# 1_zasilanie_ascii.net
KiCad netlist of a schematic drawn in Altium Designer
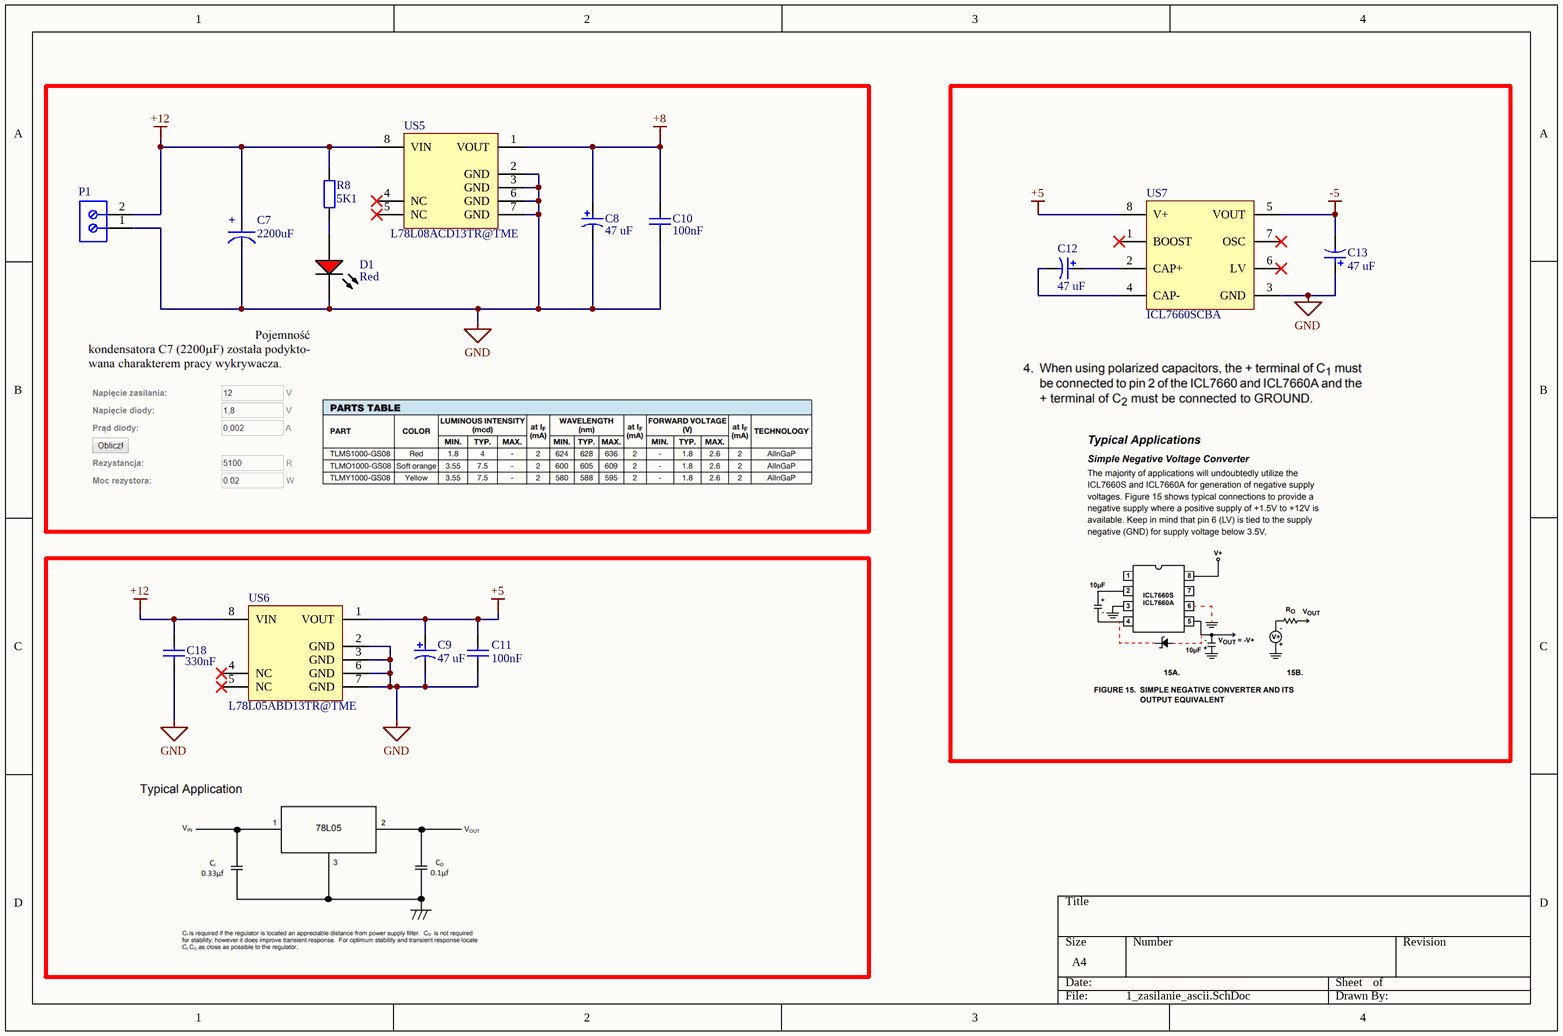
[diagram p0: 1_zasilanie_ascii.SchDoc]

(export (version "E")
  (design (tool "Eeschema 10.0.6"))
  (components
    (comp (ref "C7")
      (value "Cap Electrolytic")
      (footprint "Capacitors_MT_Library:18 X 25mm Radial 7.5mm")
      (description "CAPACITOR ALUM 2200UF 20% 35V RADIAL")
      (fields (field (name "CAPACITANCE") "2200uF"))
      (libsource (lib "MT_Library") (part "Cap Electrolytic"))
    )
    (comp (ref "C8")
      (value "UUD1E470MCL1GS")
      (footprint "NIC-CAPA2-6.3X5.8_V")
      (fields (field (name "MANUFACTURER") "Nichicon") (field (name "RATED CAPACITANCE") "47 uF"))
      (libsource (lib "Altium Content Vault") (part "NIC-CAP-P-2"))
    )
    (comp (ref "C9")
      (value "UUD1E470MCL1GS")
      (footprint "NIC-CAPA2-6.3X5.8_V")
      (fields (field (name "MANUFACTURER") "Nichicon") (field (name "RATED CAPACITANCE") "47 uF"))
      (libsource (lib "Altium Content Vault") (part "NIC-CAP-P-2"))
    )
    (comp (ref "C10")
      (value "CL10B104KA8NNNC@TME")
      (footprint "0603")
      (description "Capacitor")
      (fields (field (name "CAPACITANCE") "100nF"))
      (libsource (lib "MT_Library") (part "Cap"))
    )
    (comp (ref "C11")
      (value "CL10B104KA8NNNC@TME")
      (footprint "0603")
      (description "Capacitor")
      (fields (field (name "CAPACITANCE") "100nF"))
      (libsource (lib "MT_Library") (part "Cap"))
    )
    (comp (ref "C12")
      (value "UUD1E470MCL1GS")
      (footprint "NIC-CAPA2-6.3X5.8_V")
      (fields (field (name "MANUFACTURER") "Nichicon") (field (name "RATED CAPACITANCE") "47 uF"))
      (libsource (lib "Altium Content Vault") (part "NIC-CAP-P-2"))
    )
    (comp (ref "C13")
      (value "UUD1E470MCL1GS")
      (footprint "NIC-CAPA2-6.3X5.8_V")
      (fields (field (name "MANUFACTURER") "Nichicon") (field (name "RATED CAPACITANCE") "47 uF"))
      (libsource (lib "Altium Content Vault") (part "NIC-CAP-P-2"))
    )
    (comp (ref "C18")
      (value "330nF")
      (footprint "CAPC1608X90X35ML15T15")
      (fields
        (field (name "PART NUMBER") "0603YD334KAT2A")
        (field (name "MANUFACTURER") "AVX Interconnect / Elco")
      )
      (libsource (lib "Altium Content Vault") (part "CAP"))
    )
    (comp (ref "D1")
      (value "TLMS1000-GS08")
      (footprint "VISH-TLMS1000_V")
      (description "Low Current LED, 40 mW, 1.8 V, -40 to 100 degC, 2-Pin SMD (0603), RoHS, Tape and Reel")
      (fields (field (name "LED COLOUR") "Red") (field (name "MANUFACTURER") "Vishay"))
      (libsource (lib "Altium Content Vault") (part "LED-RED-AK-2"))
    )
    (comp (ref "P1")
      (value "282836-2@TME")
      (footprint "TECO-282836-2_V")
      (description "Female Header, Pitch 5 mm, 1 x 2 Position, Height 10 mm, Tail Length 3.5 mm, Rohs, Bulk")
      (fields (field (name "VOLTAGE") "300V") (field (name "MANUFACTURER") "TE Connectivity"))
      (libsource (lib "Altium Content Vault") (part "CN-1P-F-TB2"))
    )
    (comp (ref "R8")
      (value "5K1")
      (footprint "R1206")
      (description "Resistor")
      (fields (field (name "Comment") "1206S4J0102T5E@TME"))
      (libsource (lib "MT_Library") (part "Res"))
    )
    (comp (ref "US5")
      (value "L78L08ACD13TR@TME")
      (footprint "SO8_M")
      (description "Positive Voltage Regulator, 8V, 8-Pin SO, Tape and Reel")
      (libsource (lib "Altium Content Vault") (part "PM-REG-7805-IL8"))
    )
    (comp (ref "US6")
      (value "L78L05ABD13TR@TME")
      (footprint "SO8_N")
      (description "Positive Voltage Regulator, 5V, 8-Pin SO, Tape and Reel")
      (libsource (lib "Altium Content Vault") (part "PM-REG-7805-IL8"))
    )
    (comp (ref "US7")
      (value "ICL7660SCBA")
      (footprint "INTS-SOIC-8_V")
      (fields (field (name "MANUFACTURER") "Intersil"))
      (libsource (lib "Altium Content Vault") (part "INTS-ICL7660S-8"))
    )
  )
  (nets
    (net (code "1") (name "+5") (class "Default")
      (node (ref "C11") (pin "1") (pinfunction "1_1") (pintype "passive"))
      (node (ref "C9") (pin "1") (pinfunction "1_1") (pintype "passive"))
      (node (ref "US6") (pin "1") (pinfunction "VOUT_1") (pintype "power_in"))
      (node (ref "US7") (pin "8") (pinfunction "V+_8") (pintype "power_in"))
    )
    (net (code "2") (name "+8") (class "Default")
      (node (ref "C10") (pin "1") (pinfunction "1_1") (pintype "passive"))
      (node (ref "C8") (pin "1") (pinfunction "1_1") (pintype "passive"))
      (node (ref "US5") (pin "1") (pinfunction "VOUT_1") (pintype "power_in"))
    )
    (net (code "3") (name "+12") (class "Default")
      (node (ref "C18") (pin "1") (pinfunction "1_1") (pintype "passive"))
      (node (ref "C7") (pin "2") (pinfunction "+_2") (pintype "passive"))
      (node (ref "P1") (pin "2") (pinfunction "-_2") (pintype "power_in"))
      (node (ref "R8") (pin "2") (pinfunction "2_2") (pintype "passive"))
      (node (ref "US5") (pin "8") (pinfunction "VIN_8") (pintype "power_in"))
      (node (ref "US6") (pin "8") (pinfunction "VIN_8") (pintype "power_in"))
    )
    (net (code "4") (name "-5") (class "Default")
      (node (ref "C13") (pin "2") (pinfunction "2_2") (pintype "passive"))
      (node (ref "US7") (pin "5") (pinfunction "VOUT_5") (pintype "power_in"))
    )
    (net (code "5") (name "GND") (class "Default")
      (node (ref "C10") (pin "2") (pinfunction "2_2") (pintype "passive"))
      (node (ref "C11") (pin "2") (pinfunction "2_2") (pintype "passive"))
      (node (ref "C13") (pin "1") (pinfunction "1_1") (pintype "passive"))
      (node (ref "C18") (pin "2") (pinfunction "2_2") (pintype "passive"))
      (node (ref "C7") (pin "1") (pinfunction "-_1") (pintype "passive"))
      (node (ref "C8") (pin "2") (pinfunction "2_2") (pintype "passive"))
      (node (ref "C9") (pin "2") (pinfunction "2_2") (pintype "passive"))
      (node (ref "D1") (pin "2") (pinfunction "K_2") (pintype "passive"))
      (node (ref "P1") (pin "1") (pinfunction "+_1") (pintype "power_in"))
      (node (ref "US5") (pin "2") (pinfunction "GND_2") (pintype "power_in"))
      (node (ref "US5") (pin "3") (pinfunction "GND_3") (pintype "power_in"))
      (node (ref "US5") (pin "6") (pinfunction "GND_6") (pintype "power_in"))
      (node (ref "US5") (pin "7") (pinfunction "GND_7") (pintype "power_in"))
      (node (ref "US6") (pin "2") (pinfunction "GND_2") (pintype "power_in"))
      (node (ref "US6") (pin "3") (pinfunction "GND_3") (pintype "power_in"))
      (node (ref "US6") (pin "6") (pinfunction "GND_6") (pintype "power_in"))
      (node (ref "US6") (pin "7") (pinfunction "GND_7") (pintype "power_in"))
      (node (ref "US7") (pin "3") (pinfunction "GND_3") (pintype "power_in"))
    )
    (net (code "6") (name "Net-(D1-A)") (class "Default")
      (node (ref "D1") (pin "1") (pinfunction "A_1") (pintype "passive"))
      (node (ref "R8") (pin "1") (pinfunction "1_1") (pintype "passive"))
    )
    (net (code "7") (name "Net-(US7-CAP+)") (class "Default")
      (node (ref "C12") (pin "1") (pinfunction "1_1") (pintype "passive"))
      (node (ref "US7") (pin "2") (pinfunction "CAP+_2") (pintype "passive"))
    )
    (net (code "8") (name "Net-(US7-CAP-)") (class "Default")
      (node (ref "C12") (pin "2") (pinfunction "2_2") (pintype "passive"))
      (node (ref "US7") (pin "4") (pinfunction "CAP-_4") (pintype "passive"))
    )
    (net (code "9") (name "unconnected-(US5-NC-Pad4)") (class "Default")
      (node (ref "US5") (pin "4") (pinfunction "NC_4") (pintype "passive+no_connect"))
    )
    (net (code "10") (name "unconnected-(US5-NC-Pad5)") (class "Default")
      (node (ref "US5") (pin "5") (pinfunction "NC_5") (pintype "passive+no_connect"))
    )
    (net (code "11") (name "unconnected-(US6-NC-Pad4)") (class "Default")
      (node (ref "US6") (pin "4") (pinfunction "NC_4") (pintype "passive+no_connect"))
    )
    (net (code "12") (name "unconnected-(US6-NC-Pad5)") (class "Default")
      (node (ref "US6") (pin "5") (pinfunction "NC_5") (pintype "passive+no_connect"))
    )
    (net (code "13") (name "unconnected-(US7-BOOST-Pad1)") (class "Default")
      (node (ref "US7") (pin "1") (pinfunction "BOOST_1") (pintype "passive+no_connect"))
    )
    (net (code "14") (name "unconnected-(US7-LV-Pad6)") (class "Default")
      (node (ref "US7") (pin "6") (pinfunction "LV_6") (pintype "power_in+no_connect"))
    )
    (net (code "15") (name "unconnected-(US7-OSC-Pad7)") (class "Default")
      (node (ref "US7") (pin "7") (pinfunction "OSC_7") (pintype "passive+no_connect"))
    )
  )
)
